# driver.net
KiCad netlist of a schematic drawn in EAGLE
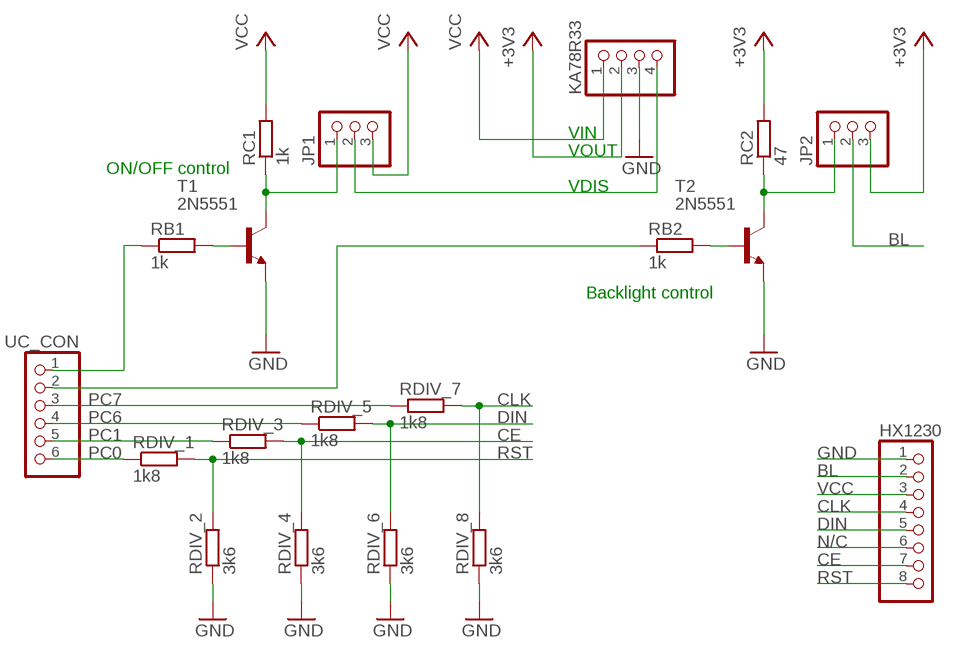
[diagram p0: schematic, sheet 1]

(export (version "E")
  (design (tool "Eeschema 10.0.6"))
  (components
    (comp (ref "HX1230")
      (value "PINHD-1X8")
      (footprint "eagle-import:1X08")
      (libsource (lib "eagle-import") (part "PINHD-1X8"))
    )
    (comp (ref "JP1")
      (value "PINHD-1X3")
      (footprint "eagle-import:1X03")
      (libsource (lib "eagle-import") (part "PINHD-1X3"))
    )
    (comp (ref "JP2")
      (value "PINHD-1X3")
      (footprint "eagle-import:1X03")
      (libsource (lib "eagle-import") (part "PINHD-1X3"))
    )
    (comp (ref "KA78R33")
      (value "PINHD-1X4")
      (footprint "eagle-import:1X04")
      (libsource (lib "eagle-import") (part "PINHD-1X4"))
    )
    (comp (ref "RB1")
      (value "1k")
      (footprint "eagle-import:0207_10")
      (libsource (lib "eagle-import") (part "R-EU_0207/10"))
    )
    (comp (ref "RB2")
      (value "1k")
      (footprint "eagle-import:0207_10")
      (libsource (lib "eagle-import") (part "R-EU_0207/10"))
    )
    (comp (ref "RC1")
      (value "1k")
      (footprint "eagle-import:0207_10")
      (libsource (lib "eagle-import") (part "R-EU_0207/10"))
    )
    (comp (ref "RC2")
      (value "47")
      (footprint "eagle-import:0207_10")
      (libsource (lib "eagle-import") (part "R-EU_0207/10"))
    )
    (comp (ref "RDIV_1")
      (value "1k8")
      (footprint "eagle-import:0207_10")
      (libsource (lib "eagle-import") (part "R-EU_0207/10"))
    )
    (comp (ref "RDIV_2")
      (value "3k6")
      (footprint "eagle-import:0207_10")
      (libsource (lib "eagle-import") (part "R-EU_0207/10"))
    )
    (comp (ref "RDIV_3")
      (value "1k8")
      (footprint "eagle-import:0207_10")
      (libsource (lib "eagle-import") (part "R-EU_0207/10"))
    )
    (comp (ref "RDIV_4")
      (value "3k6")
      (footprint "eagle-import:0207_10")
      (libsource (lib "eagle-import") (part "R-EU_0207/10"))
    )
    (comp (ref "RDIV_5")
      (value "1k8")
      (footprint "eagle-import:0207_10")
      (libsource (lib "eagle-import") (part "R-EU_0207/10"))
    )
    (comp (ref "RDIV_6")
      (value "3k6")
      (footprint "eagle-import:0207_10")
      (libsource (lib "eagle-import") (part "R-EU_0207/10"))
    )
    (comp (ref "RDIV_7")
      (value "1k8")
      (footprint "eagle-import:0207_10")
      (libsource (lib "eagle-import") (part "R-EU_0207/10"))
    )
    (comp (ref "RDIV_8")
      (value "3k6")
      (footprint "eagle-import:0207_10")
      (libsource (lib "eagle-import") (part "R-EU_0207/10"))
    )
    (comp (ref "T1")
      (value "2N5551")
      (footprint "eagle-import:TO92-EBC")
      (libsource (lib "eagle-import") (part "-NPN-TO92-EBC2N5551"))
    )
    (comp (ref "T2")
      (value "2N5551")
      (footprint "eagle-import:TO92-EBC")
      (libsource (lib "eagle-import") (part "-NPN-TO92-EBC2N5551"))
    )
    (comp (ref "UC_CON")
      (value "PINHD-1X6")
      (footprint "eagle-import:1X06")
      (libsource (lib "eagle-import") (part "PINHD-1X6"))
    )
  )
  (nets
    (net (code "1") (name "+3V3") (class "Default")
      (node (ref "JP2") (pin "3") (pinfunction "3_3") (pintype "passive"))
      (node (ref "KA78R33") (pin "2") (pinfunction "2_2") (pintype "passive"))
      (node (ref "RC2") (pin "2") (pinfunction "2_2") (pintype "passive"))
    )
    (net (code "2") (name "/BL") (class "Default")
      (node (ref "HX1230") (pin "2") (pinfunction "2_2") (pintype "passive"))
      (node (ref "JP2") (pin "2") (pinfunction "2_2") (pintype "passive"))
    )
    (net (code "3") (name "/CE") (class "Default")
      (node (ref "HX1230") (pin "7") (pinfunction "7_7") (pintype "passive"))
      (node (ref "RDIV_3") (pin "2") (pinfunction "2_2") (pintype "passive"))
      (node (ref "RDIV_4") (pin "2") (pinfunction "2_2") (pintype "passive"))
    )
    (net (code "4") (name "/CLK") (class "Default")
      (node (ref "HX1230") (pin "4") (pinfunction "4_4") (pintype "passive"))
      (node (ref "RDIV_7") (pin "2") (pinfunction "2_2") (pintype "passive"))
      (node (ref "RDIV_8") (pin "2") (pinfunction "2_2") (pintype "passive"))
    )
    (net (code "5") (name "/DIN") (class "Default")
      (node (ref "HX1230") (pin "5") (pinfunction "5_5") (pintype "passive"))
      (node (ref "RDIV_5") (pin "2") (pinfunction "2_2") (pintype "passive"))
      (node (ref "RDIV_6") (pin "2") (pinfunction "2_2") (pintype "passive"))
    )
    (net (code "6") (name "/N{slash}C") (class "Default")
      (node (ref "HX1230") (pin "6") (pinfunction "6_6") (pintype "passive"))
    )
    (net (code "7") (name "/PC0") (class "Default")
      (node (ref "RDIV_1") (pin "1") (pinfunction "1_1") (pintype "passive"))
      (node (ref "UC_CON") (pin "6") (pinfunction "6_6") (pintype "passive"))
    )
    (net (code "8") (name "/PC1") (class "Default")
      (node (ref "RDIV_3") (pin "1") (pinfunction "1_1") (pintype "passive"))
      (node (ref "UC_CON") (pin "5") (pinfunction "5_5") (pintype "passive"))
    )
    (net (code "9") (name "/PC6") (class "Default")
      (node (ref "RDIV_5") (pin "1") (pinfunction "1_1") (pintype "passive"))
      (node (ref "UC_CON") (pin "4") (pinfunction "4_4") (pintype "passive"))
    )
    (net (code "10") (name "/PC7") (class "Default")
      (node (ref "RDIV_7") (pin "1") (pinfunction "1_1") (pintype "passive"))
      (node (ref "UC_CON") (pin "3") (pinfunction "3_3") (pintype "passive"))
    )
    (net (code "11") (name "/RST") (class "Default")
      (node (ref "HX1230") (pin "8") (pinfunction "8_8") (pintype "passive"))
      (node (ref "RDIV_1") (pin "2") (pinfunction "2_2") (pintype "passive"))
      (node (ref "RDIV_2") (pin "2") (pinfunction "2_2") (pintype "passive"))
    )
    (net (code "12") (name "GND") (class "Default")
      (node (ref "HX1230") (pin "1") (pinfunction "1_1") (pintype "passive"))
      (node (ref "KA78R33") (pin "3") (pinfunction "3_3") (pintype "passive"))
      (node (ref "RDIV_2") (pin "1") (pinfunction "1_1") (pintype "passive"))
      (node (ref "RDIV_4") (pin "1") (pinfunction "1_1") (pintype "passive"))
      (node (ref "RDIV_6") (pin "1") (pinfunction "1_1") (pintype "passive"))
      (node (ref "RDIV_8") (pin "1") (pinfunction "1_1") (pintype "passive"))
      (node (ref "T1") (pin "E") (pinfunction "E_E") (pintype "passive"))
      (node (ref "T2") (pin "E") (pinfunction "E_E") (pintype "passive"))
    )
    (net (code "13") (name "Net-(JP1-Pad1)") (class "Default")
      (node (ref "JP1") (pin "1") (pinfunction "1_1") (pintype "passive"))
      (node (ref "RC1") (pin "1") (pinfunction "1_1") (pintype "passive"))
      (node (ref "T1") (pin "C") (pinfunction "C_C") (pintype "passive"))
    )
    (net (code "14") (name "Net-(JP1-Pad2)") (class "Default")
      (node (ref "JP1") (pin "2") (pinfunction "2_2") (pintype "passive"))
      (node (ref "KA78R33") (pin "4") (pinfunction "4_4") (pintype "passive"))
    )
    (net (code "15") (name "Net-(JP2-Pad1)") (class "Default")
      (node (ref "JP2") (pin "1") (pinfunction "1_1") (pintype "passive"))
      (node (ref "RC2") (pin "1") (pinfunction "1_1") (pintype "passive"))
      (node (ref "T2") (pin "C") (pinfunction "C_C") (pintype "passive"))
    )
    (net (code "16") (name "Net-(RB1-Pad1)") (class "Default")
      (node (ref "RB1") (pin "1") (pinfunction "1_1") (pintype "passive"))
      (node (ref "UC_CON") (pin "1") (pinfunction "1_1") (pintype "passive"))
    )
    (net (code "17") (name "Net-(RB1-Pad2)") (class "Default")
      (node (ref "RB1") (pin "2") (pinfunction "2_2") (pintype "passive"))
      (node (ref "T1") (pin "B") (pinfunction "B_B") (pintype "passive"))
    )
    (net (code "18") (name "Net-(RB2-Pad1)") (class "Default")
      (node (ref "RB2") (pin "1") (pinfunction "1_1") (pintype "passive"))
      (node (ref "UC_CON") (pin "2") (pinfunction "2_2") (pintype "passive"))
    )
    (net (code "19") (name "Net-(RB2-Pad2)") (class "Default")
      (node (ref "RB2") (pin "2") (pinfunction "2_2") (pintype "passive"))
      (node (ref "T2") (pin "B") (pinfunction "B_B") (pintype "passive"))
    )
    (net (code "20") (name "VCC") (class "Default")
      (node (ref "HX1230") (pin "3") (pinfunction "3_3") (pintype "passive"))
      (node (ref "JP1") (pin "3") (pinfunction "3_3") (pintype "passive"))
      (node (ref "KA78R33") (pin "1") (pinfunction "1_1") (pintype "passive"))
      (node (ref "RC1") (pin "2") (pinfunction "2_2") (pintype "passive"))
    )
  )
)
